# PIC32.net
KiCad netlist of a schematic drawn in EAGLE
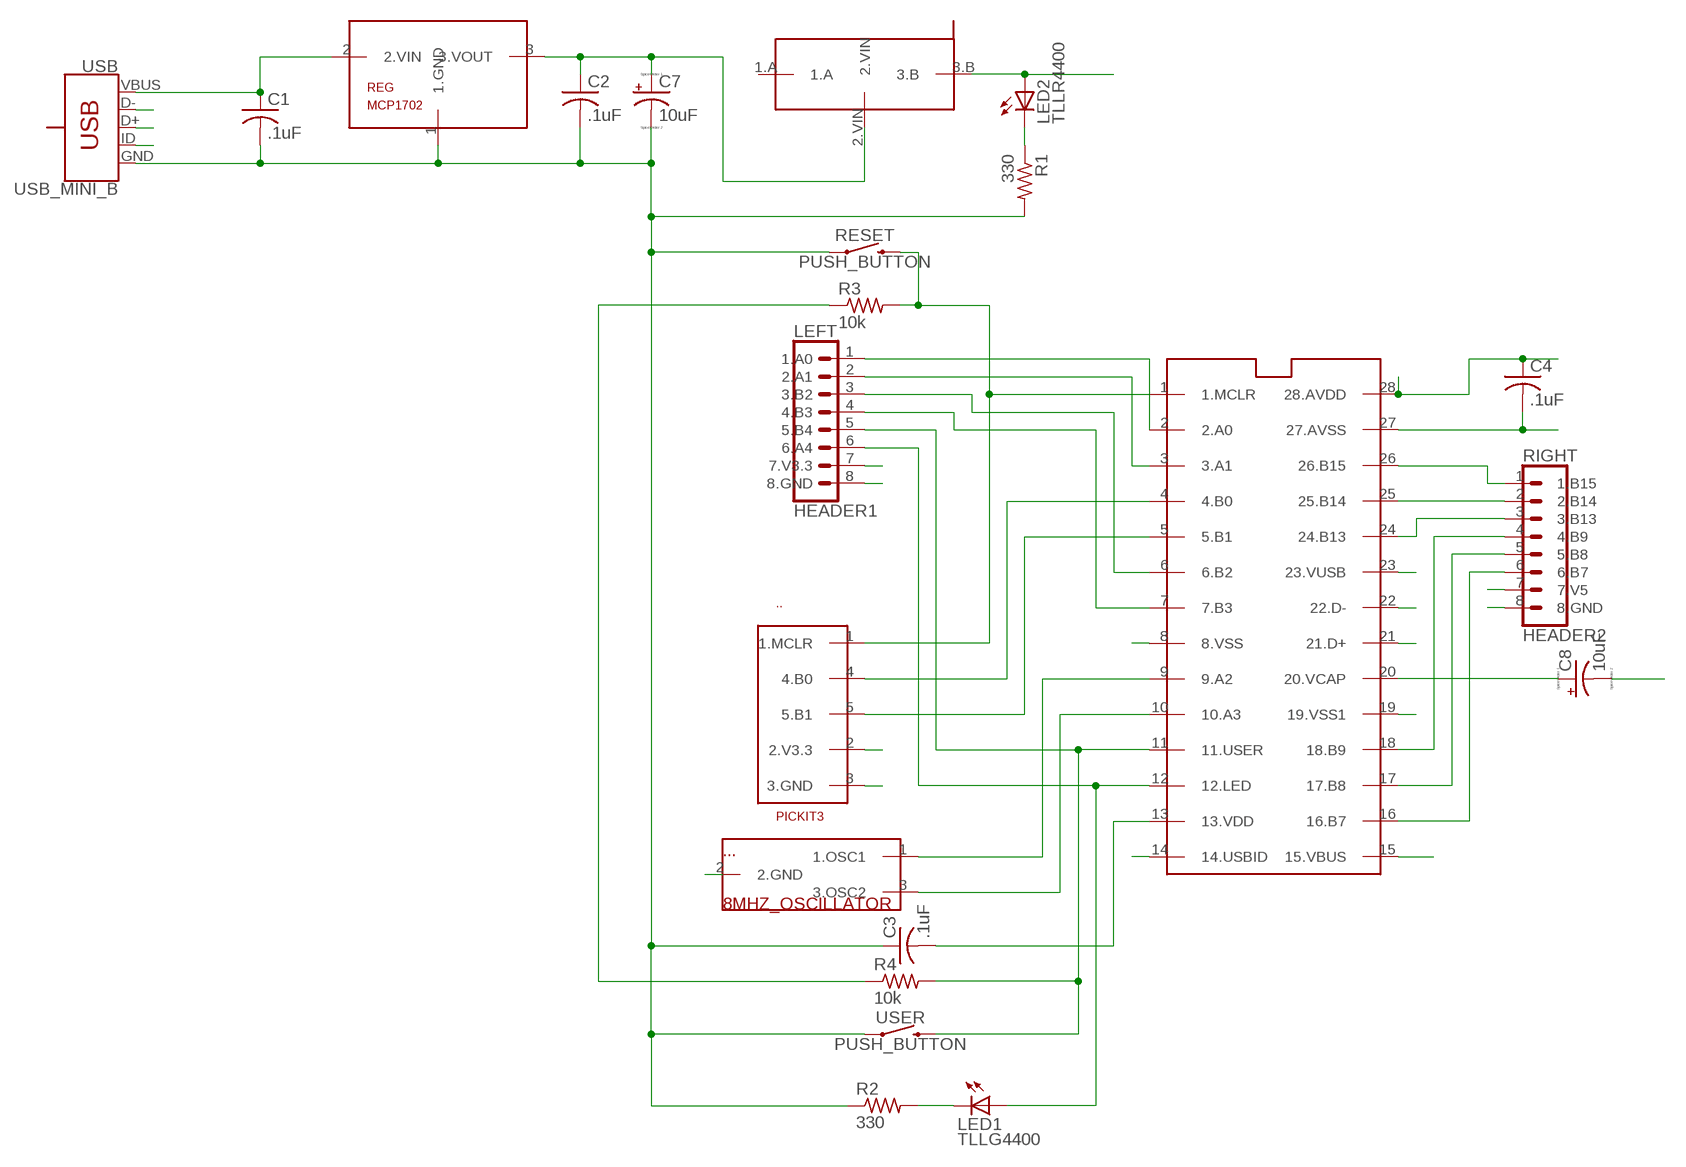
[diagram p0: schematic, sheet 1]

(export (version "E")
  (design (tool "Eeschema 10.0.6"))
  (components
    (comp (ref "..")
      (value "PICKIT3")
      (footprint "eagle-import:1X05")
      (libsource (lib "eagle-import") (part "PICKIT3"))
    )
    (comp (ref "...")
      (value "8MHZ_OSCILLATOR")
      (footprint "eagle-import:1X03")
      (libsource (lib "eagle-import") (part "8MHZ_OSCILLATOR"))
    )
    (comp (ref "C1")
      (value ".1uF")
      (footprint "eagle-import:C025-025X050")
      (libsource (lib "eagle-import") (part "C-US025-025X050"))
    )
    (comp (ref "C2")
      (value ".1uF")
      (footprint "eagle-import:C025-025X050")
      (libsource (lib "eagle-import") (part "C-US025-025X050"))
    )
    (comp (ref "C3")
      (value ".1uF")
      (footprint "eagle-import:C025-025X050")
      (libsource (lib "eagle-import") (part "C-US025-025X050"))
    )
    (comp (ref "C4")
      (value ".1uF")
      (footprint "eagle-import:C025-025X050")
      (libsource (lib "eagle-import") (part "C-US025-025X050"))
    )
    (comp (ref "C7")
      (value "10uF")
      (footprint "eagle-import:E5-8,5")
      (libsource (lib "eagle-import") (part "CPOL-USE5-8.5"))
    )
    (comp (ref "C8")
      (value "10uF")
      (footprint "eagle-import:E5-8,5")
      (libsource (lib "eagle-import") (part "CPOL-USE5-8.5"))
    )
    (comp (ref "DIP_28")
      (value "PIC32MX250F128_DIP")
      (footprint "eagle-import:DIL28-3")
      (libsource (lib "eagle-import") (part "PIC32MX250F128_DIP"))
    )
    (comp (ref "LED1")
      (value "TLLG4400")
      (footprint "eagle-import:LED3MM")
      (fields (field (name "MF") "VISHAY SEMICONDUCTOR"))
      (libsource (lib "eagle-import") (part "TLLG4400"))
    )
    (comp (ref "LED2")
      (value "TLLR4400")
      (footprint "eagle-import:LED3MM")
      (fields (field (name "MF") "VISHAY SEMICONDUCTOR"))
      (libsource (lib "eagle-import") (part "TLLR4400"))
    )
    (comp (ref "LEFT")
      (value "HEADER1")
      (footprint "eagle-import:1X08")
      (libsource (lib "eagle-import") (part "HEADER1"))
    )
    (comp (ref "R1")
      (value "330")
      (footprint "eagle-import:0207_10")
      (libsource (lib "eagle-import") (part "R-US_0207/10"))
    )
    (comp (ref "R2")
      (value "330")
      (footprint "eagle-import:0207_10")
      (libsource (lib "eagle-import") (part "R-US_0207/10"))
    )
    (comp (ref "R3")
      (value "10k")
      (footprint "eagle-import:0207_10")
      (libsource (lib "eagle-import") (part "R-US_0207/10"))
    )
    (comp (ref "R4")
      (value "10k")
      (footprint "eagle-import:0207_10")
      (libsource (lib "eagle-import") (part "R-US_0207/10"))
    )
    (comp (ref "REG")
      (value "MCP1702")
      (footprint "eagle-import:TO92")
      (libsource (lib "eagle-import") (part "MCP1702"))
    )
    (comp (ref "RESET")
      (value "PUSH_BUTTON")
      (footprint "eagle-import:PB")
      (libsource (lib "eagle-import") (part "PUSH_BUTTON"))
    )
    (comp (ref "RIGHT")
      (value "HEADER2")
      (footprint "eagle-import:1X08")
      (libsource (lib "eagle-import") (part "HEADER2"))
    )
    (comp (ref "U$5")
      (value "SLIDE_SWITCH")
      (footprint "eagle-import:SLIDE_SWITCH")
      (libsource (lib "eagle-import") (part "SLIDE_SWITCH"))
    )
    (comp (ref "USB")
      (value "USB_MINI_B")
      (footprint "eagle-import:USB-MB-H")
      (libsource (lib "eagle-import") (part "USB_MINI_B"))
    )
    (comp (ref "USER")
      (value "PUSH_BUTTON")
      (footprint "eagle-import:PB")
      (libsource (lib "eagle-import") (part "PUSH_BUTTON"))
    )
  )
  (nets
    (net (code "1") (name "/D+") (class "Default")
      (node (ref "DIP_28") (pin "21") (pinfunction "21.D+_21") (pintype "bidirectional"))
      (node (ref "USB") (pin "D+") (pinfunction "3.D+_D+") (pintype "bidirectional"))
    )
    (net (code "2") (name "/D-") (class "Default")
      (node (ref "DIP_28") (pin "22") (pinfunction "22.D-_22") (pintype "bidirectional"))
      (node (ref "USB") (pin "D-") (pinfunction "2.D-_D-") (pintype "bidirectional"))
    )
    (net (code "3") (name "/GND") (class "Default")
      (node (ref "..") (pin "3") (pinfunction "3.GND_3") (pintype "bidirectional"))
      (node (ref "...") (pin "2") (pinfunction "2.GND_2") (pintype "bidirectional"))
      (node (ref "C1") (pin "2") (pinfunction "2_2") (pintype "passive"))
      (node (ref "C2") (pin "2") (pinfunction "2_2") (pintype "passive"))
      (node (ref "C3") (pin "1") (pinfunction "1_1") (pintype "passive"))
      (node (ref "C4") (pin "2") (pinfunction "2_2") (pintype "passive"))
      (node (ref "C7") (pin "-") (pinfunction "-_-") (pintype "passive"))
      (node (ref "C8") (pin "-") (pinfunction "-_-") (pintype "passive"))
      (node (ref "DIP_28") (pin "27") (pinfunction "27.AVSS_27") (pintype "bidirectional"))
      (node (ref "DIP_28") (pin "8") (pinfunction "8.VSS_8") (pintype "bidirectional"))
      (node (ref "LEFT") (pin "8") (pinfunction "8.GND_8") (pintype "passive"))
      (node (ref "R1") (pin "2") (pinfunction "2_2") (pintype "passive"))
      (node (ref "R2") (pin "1") (pinfunction "1_1") (pintype "passive"))
      (node (ref "REG") (pin "1") (pinfunction "1.GND_1") (pintype "bidirectional"))
      (node (ref "RESET") (pin "1") (pinfunction "1_1") (pintype "passive"))
      (node (ref "RIGHT") (pin "8") (pinfunction "8.GND_8") (pintype "passive"))
      (node (ref "USB") (pin "GND") (pinfunction "5.GND_GND") (pintype "power_in"))
      (node (ref "USER") (pin "1") (pinfunction "1_1") (pintype "passive"))
    )
    (net (code "4") (name "/ID") (class "Default")
      (node (ref "DIP_28") (pin "14") (pinfunction "14.USBID_14") (pintype "bidirectional"))
      (node (ref "USB") (pin "ID") (pinfunction "4.ID_ID") (pintype "bidirectional"))
    )
    (net (code "5") (name "/V3.3") (class "Default")
      (node (ref "..") (pin "2") (pinfunction "2.V3.3_2") (pintype "bidirectional"))
      (node (ref "C3") (pin "2") (pinfunction "2_2") (pintype "passive"))
      (node (ref "C4") (pin "1") (pinfunction "1_1") (pintype "passive"))
      (node (ref "DIP_28") (pin "13") (pinfunction "13.VDD_13") (pintype "bidirectional"))
      (node (ref "DIP_28") (pin "19") (pinfunction "19.VSS1_19") (pintype "bidirectional"))
      (node (ref "DIP_28") (pin "23") (pinfunction "23.VUSB_23") (pintype "bidirectional"))
      (node (ref "DIP_28") (pin "28") (pinfunction "28.AVDD_28") (pintype "bidirectional"))
      (node (ref "LED2") (pin "A") (pinfunction "A_A") (pintype "passive"))
      (node (ref "LEFT") (pin "7") (pinfunction "7.V3.3_7") (pintype "passive"))
      (node (ref "R3") (pin "1") (pinfunction "1_1") (pintype "passive"))
      (node (ref "R4") (pin "1") (pinfunction "1_1") (pintype "passive"))
      (node (ref "U$5") (pin "3.B") (pinfunction "3.B_3.B") (pintype "bidirectional"))
    )
    (net (code "6") (name "/VBUS") (class "Default")
      (node (ref "C1") (pin "1") (pinfunction "1_1") (pintype "passive"))
      (node (ref "DIP_28") (pin "15") (pinfunction "15.VBUS_15") (pintype "bidirectional"))
      (node (ref "REG") (pin "2") (pinfunction "2.VIN_2") (pintype "bidirectional"))
      (node (ref "RIGHT") (pin "7") (pinfunction "7.V5_7") (pintype "passive"))
      (node (ref "USB") (pin "VBUS") (pinfunction "1.VBUS_VBUS") (pintype "power_in"))
    )
    (net (code "7") (name "Net-(..-1.MCLR)") (class "Default")
      (node (ref "..") (pin "1") (pinfunction "1.MCLR_1") (pintype "bidirectional"))
      (node (ref "DIP_28") (pin "1") (pinfunction "1.MCLR_1") (pintype "bidirectional"))
      (node (ref "R3") (pin "2") (pinfunction "2_2") (pintype "passive"))
      (node (ref "RESET") (pin "2") (pinfunction "2_2") (pintype "passive"))
    )
    (net (code "8") (name "Net-(..-4.B0)") (class "Default")
      (node (ref "..") (pin "4") (pinfunction "4.B0_4") (pintype "bidirectional"))
      (node (ref "DIP_28") (pin "4") (pinfunction "4.B0_4") (pintype "bidirectional"))
    )
    (net (code "9") (name "Net-(..-5.B1)") (class "Default")
      (node (ref "..") (pin "5") (pinfunction "5.B1_5") (pintype "bidirectional"))
      (node (ref "DIP_28") (pin "5") (pinfunction "5.B1_5") (pintype "bidirectional"))
    )
    (net (code "10") (name "Net-(...-1.OSC1)") (class "Default")
      (node (ref "...") (pin "1") (pinfunction "1.OSC1_1") (pintype "bidirectional"))
      (node (ref "DIP_28") (pin "9") (pinfunction "9.A2_9") (pintype "bidirectional"))
    )
    (net (code "11") (name "Net-(...-3.OSC2)") (class "Default")
      (node (ref "...") (pin "3") (pinfunction "3.OSC2_3") (pintype "bidirectional"))
      (node (ref "DIP_28") (pin "10") (pinfunction "10.A3_10") (pintype "bidirectional"))
    )
    (net (code "12") (name "Net-(DIP_28-2.A0)") (class "Default")
      (node (ref "DIP_28") (pin "2") (pinfunction "2.A0_2") (pintype "bidirectional"))
      (node (ref "LEFT") (pin "1") (pinfunction "1.A0_1") (pintype "passive"))
    )
    (net (code "13") (name "Net-(DIP_28-3.A1)") (class "Default")
      (node (ref "DIP_28") (pin "3") (pinfunction "3.A1_3") (pintype "bidirectional"))
      (node (ref "LEFT") (pin "2") (pinfunction "2.A1_2") (pintype "passive"))
    )
    (net (code "14") (name "Net-(DIP_28-6.B2)") (class "Default")
      (node (ref "DIP_28") (pin "6") (pinfunction "6.B2_6") (pintype "bidirectional"))
      (node (ref "LEFT") (pin "3") (pinfunction "3.B2_3") (pintype "passive"))
    )
    (net (code "15") (name "Net-(DIP_28-7.B3)") (class "Default")
      (node (ref "DIP_28") (pin "7") (pinfunction "7.B3_7") (pintype "bidirectional"))
      (node (ref "LEFT") (pin "4") (pinfunction "4.B3_4") (pintype "passive"))
    )
    (net (code "16") (name "Net-(DIP_28-11.USER)") (class "Default")
      (node (ref "DIP_28") (pin "11") (pinfunction "11.USER_11") (pintype "bidirectional"))
      (node (ref "LEFT") (pin "5") (pinfunction "5.B4_5") (pintype "passive"))
      (node (ref "R4") (pin "2") (pinfunction "2_2") (pintype "passive"))
      (node (ref "USER") (pin "2") (pinfunction "2_2") (pintype "passive"))
    )
    (net (code "17") (name "Net-(DIP_28-12.LED)") (class "Default")
      (node (ref "DIP_28") (pin "12") (pinfunction "12.LED_12") (pintype "bidirectional"))
      (node (ref "LED1") (pin "A") (pinfunction "A_A") (pintype "passive"))
      (node (ref "LEFT") (pin "6") (pinfunction "6.A4_6") (pintype "passive"))
    )
    (net (code "18") (name "Net-(DIP_28-16.B7)") (class "Default")
      (node (ref "DIP_28") (pin "16") (pinfunction "16.B7_16") (pintype "bidirectional"))
      (node (ref "RIGHT") (pin "6") (pinfunction "6.B7_6") (pintype "passive"))
    )
    (net (code "19") (name "Net-(DIP_28-17.B8)") (class "Default")
      (node (ref "DIP_28") (pin "17") (pinfunction "17.B8_17") (pintype "bidirectional"))
      (node (ref "RIGHT") (pin "5") (pinfunction "5.B8_5") (pintype "passive"))
    )
    (net (code "20") (name "Net-(DIP_28-18.B9)") (class "Default")
      (node (ref "DIP_28") (pin "18") (pinfunction "18.B9_18") (pintype "bidirectional"))
      (node (ref "RIGHT") (pin "4") (pinfunction "4.B9_4") (pintype "passive"))
    )
    (net (code "21") (name "Net-(DIP_28-20.VCAP)") (class "Default")
      (node (ref "C8") (pin "+") (pinfunction "+_+") (pintype "passive"))
      (node (ref "DIP_28") (pin "20") (pinfunction "20.VCAP_20") (pintype "bidirectional"))
    )
    (net (code "22") (name "Net-(DIP_28-24.B13)") (class "Default")
      (node (ref "DIP_28") (pin "24") (pinfunction "24.B13_24") (pintype "bidirectional"))
      (node (ref "RIGHT") (pin "3") (pinfunction "3.B13_3") (pintype "passive"))
    )
    (net (code "23") (name "Net-(DIP_28-25.B14)") (class "Default")
      (node (ref "DIP_28") (pin "25") (pinfunction "25.B14_25") (pintype "bidirectional"))
      (node (ref "RIGHT") (pin "2") (pinfunction "2.B14_2") (pintype "passive"))
    )
    (net (code "24") (name "Net-(DIP_28-26.B15)") (class "Default")
      (node (ref "DIP_28") (pin "26") (pinfunction "26.B15_26") (pintype "bidirectional"))
      (node (ref "RIGHT") (pin "1") (pinfunction "1.B15_1") (pintype "passive"))
    )
    (net (code "25") (name "Net-(LED1-C)") (class "Default")
      (node (ref "LED1") (pin "K") (pinfunction "C_K") (pintype "passive"))
      (node (ref "R2") (pin "2") (pinfunction "2_2") (pintype "passive"))
    )
    (net (code "26") (name "Net-(LED2-C)") (class "Default")
      (node (ref "LED2") (pin "K") (pinfunction "C_K") (pintype "passive"))
      (node (ref "R1") (pin "1") (pinfunction "1_1") (pintype "passive"))
    )
    (net (code "27") (name "Net-(REG-3.VOUT)") (class "Default")
      (node (ref "C2") (pin "1") (pinfunction "1_1") (pintype "passive"))
      (node (ref "C7") (pin "+") (pinfunction "+_+") (pintype "passive"))
      (node (ref "REG") (pin "3") (pinfunction "3.VOUT_3") (pintype "bidirectional"))
      (node (ref "U$5") (pin "2.VIN") (pinfunction "2.VIN_2.VIN") (pintype "bidirectional"))
    )
    (net (code "28") (name "unconnected-(U$5-Pad1.A)") (class "Default")
      (node (ref "U$5") (pin "1.A") (pinfunction "1.A_1.A") (pintype "bidirectional"))
    )
  )
)
